# Storage.net
KiCad netlist of a schematic drawn in Altium Designer
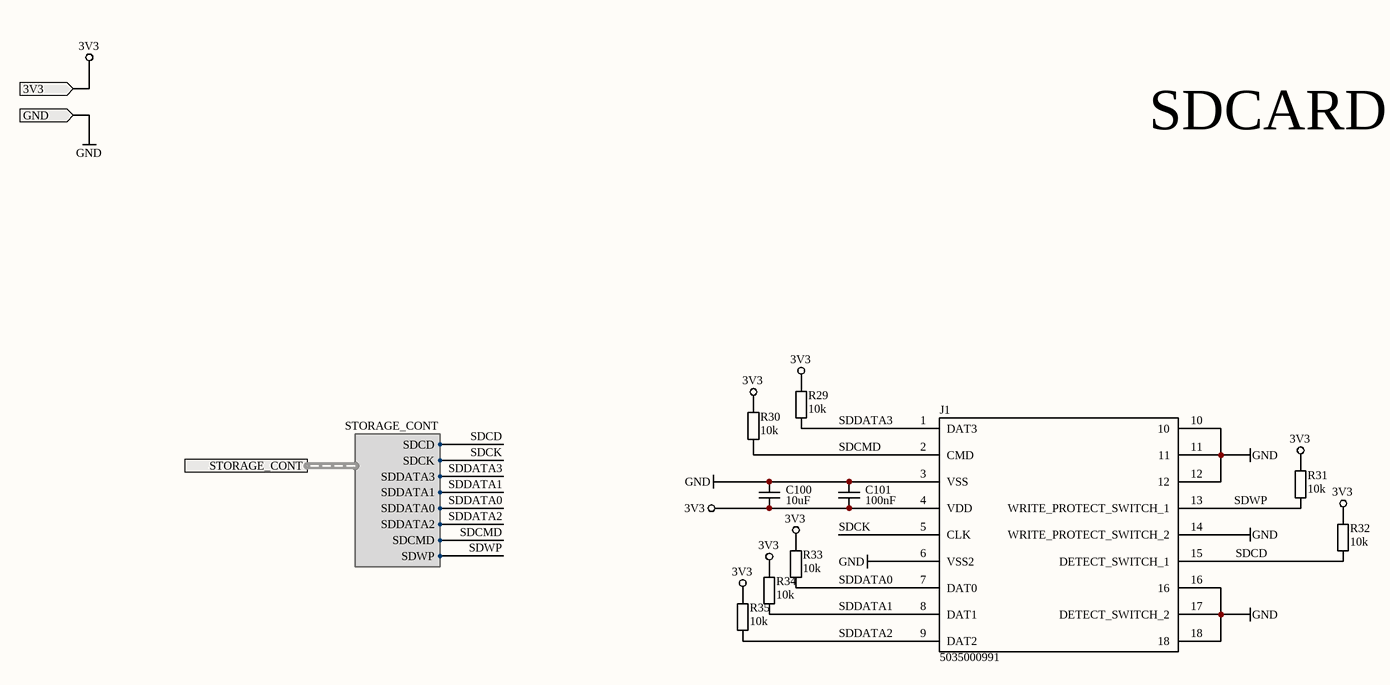
[diagram p0: Storage.SchDoc]

(export (version "E")
  (design (tool "Eeschema 10.0.6"))
  (components
    (comp (ref "C100")
      (value "10uF")
      (footprint "C_0805")
      (description "10uF 10V X7R")
      (libsource (lib "SchematicLibrary") (part "GCJ21BR71A106KE01L"))
    )
    (comp (ref "C101")
      (value "100nF")
      (footprint "C_0402")
      (description "100nF 10V 0402 X7R")
      (libsource (lib "SchematicLibrary") (part "C0402C104J8RACAUTO"))
    )
    (comp (ref "J1")
      (value "5035000991")
      (footprint "5035000991")
      (description "SD Card Connector")
      (libsource (lib "SchematicLibrary") (part "5035000991"))
    )
    (comp (ref "R29")
      (value "10k")
      (footprint "R_0402")
      (description "10k 1% 62.5mW")
      (libsource (lib "SchematicLibrary") (part "SFR01MZPF1002"))
    )
    (comp (ref "R30")
      (value "10k")
      (footprint "R_0402")
      (description "10k 1% 62.5mW")
      (libsource (lib "SchematicLibrary") (part "SFR01MZPF1002"))
    )
    (comp (ref "R31")
      (value "10k")
      (footprint "R_0402")
      (description "10k 1% 62.5mW")
      (libsource (lib "SchematicLibrary") (part "SFR01MZPF1002"))
    )
    (comp (ref "R32")
      (value "10k")
      (footprint "R_0402")
      (description "10k 1% 62.5mW")
      (libsource (lib "SchematicLibrary") (part "SFR01MZPF1002"))
    )
    (comp (ref "R33")
      (value "10k")
      (footprint "R_0402")
      (description "10k 1% 62.5mW")
      (libsource (lib "SchematicLibrary") (part "SFR01MZPF1002"))
    )
    (comp (ref "R34")
      (value "10k")
      (footprint "R_0402")
      (description "10k 1% 62.5mW")
      (libsource (lib "SchematicLibrary") (part "SFR01MZPF1002"))
    )
    (comp (ref "R35")
      (value "10k")
      (footprint "R_0402")
      (description "10k 1% 62.5mW")
      (libsource (lib "SchematicLibrary") (part "SFR01MZPF1002"))
    )
  )
  (nets
    (net (code "2") (name "/SDCD") (class "Default")
      (node (ref "J1") (pin "15") (pinfunction "DETECT_SWITCH_1_15") (pintype "passive"))
      (node (ref "R32") (pin "1") (pinfunction "1_1") (pintype "passive"))
    )
    (net (code "3") (name "/SDCK") (class "Default")
      (node (ref "J1") (pin "5") (pinfunction "CLK_5") (pintype "passive"))
    )
    (net (code "4") (name "/SDCMD") (class "Default")
      (node (ref "J1") (pin "2") (pinfunction "CMD_2") (pintype "passive"))
      (node (ref "R30") (pin "1") (pinfunction "1_1") (pintype "passive"))
    )
    (net (code "5") (name "/SDDATA0") (class "Default")
      (node (ref "J1") (pin "7") (pinfunction "DAT0_7") (pintype "passive"))
      (node (ref "R33") (pin "1") (pinfunction "1_1") (pintype "passive"))
    )
    (net (code "6") (name "/SDDATA1") (class "Default")
      (node (ref "J1") (pin "8") (pinfunction "DAT1_8") (pintype "passive"))
      (node (ref "R34") (pin "1") (pinfunction "1_1") (pintype "passive"))
    )
    (net (code "7") (name "/SDDATA2") (class "Default")
      (node (ref "J1") (pin "9") (pinfunction "DAT2_9") (pintype "passive"))
      (node (ref "R35") (pin "1") (pinfunction "1_1") (pintype "passive"))
    )
    (net (code "8") (name "/SDDATA3") (class "Default")
      (node (ref "J1") (pin "1") (pinfunction "DAT3_1") (pintype "passive"))
      (node (ref "R29") (pin "1") (pinfunction "1_1") (pintype "passive"))
    )
    (net (code "9") (name "/SDWP") (class "Default")
      (node (ref "J1") (pin "13") (pinfunction "WRITE_PROTECT_SWITCH_1_13") (pintype "passive"))
      (node (ref "R31") (pin "1") (pinfunction "1_1") (pintype "passive"))
    )
    (net (code "11") (name "3V3") (class "Default")
      (node (ref "C100") (pin "2") (pinfunction "2_2") (pintype "passive"))
      (node (ref "C101") (pin "1") (pinfunction "1_1") (pintype "passive"))
      (node (ref "J1") (pin "4") (pinfunction "VDD_4") (pintype "passive"))
      (node (ref "R29") (pin "2") (pinfunction "2_2") (pintype "passive"))
      (node (ref "R30") (pin "2") (pinfunction "2_2") (pintype "passive"))
      (node (ref "R31") (pin "2") (pinfunction "2_2") (pintype "passive"))
      (node (ref "R32") (pin "2") (pinfunction "2_2") (pintype "passive"))
      (node (ref "R33") (pin "2") (pinfunction "2_2") (pintype "passive"))
      (node (ref "R34") (pin "2") (pinfunction "2_2") (pintype "passive"))
      (node (ref "R35") (pin "2") (pinfunction "2_2") (pintype "passive"))
    )
    (net (code "12") (name "GND") (class "Default")
      (node (ref "C100") (pin "1") (pinfunction "1_1") (pintype "passive"))
      (node (ref "C101") (pin "2") (pinfunction "2_2") (pintype "passive"))
      (node (ref "J1") (pin "10") (pinfunction "10_10") (pintype "passive"))
      (node (ref "J1") (pin "11") (pinfunction "11_11") (pintype "passive"))
      (node (ref "J1") (pin "12") (pinfunction "12_12") (pintype "passive"))
      (node (ref "J1") (pin "14") (pinfunction "WRITE_PROTECT_SWITCH_2_14") (pintype "passive"))
      (node (ref "J1") (pin "16") (pinfunction "16_16") (pintype "passive"))
      (node (ref "J1") (pin "17") (pinfunction "DETECT_SWITCH_2_17") (pintype "passive"))
      (node (ref "J1") (pin "18") (pinfunction "18_18") (pintype "passive"))
      (node (ref "J1") (pin "3") (pinfunction "VSS_3") (pintype "passive"))
      (node (ref "J1") (pin "6") (pinfunction "VSS2_6") (pintype "passive"))
    )
  )
)
